# untitled.net
KiCad netlist of a schematic drawn in EAGLE
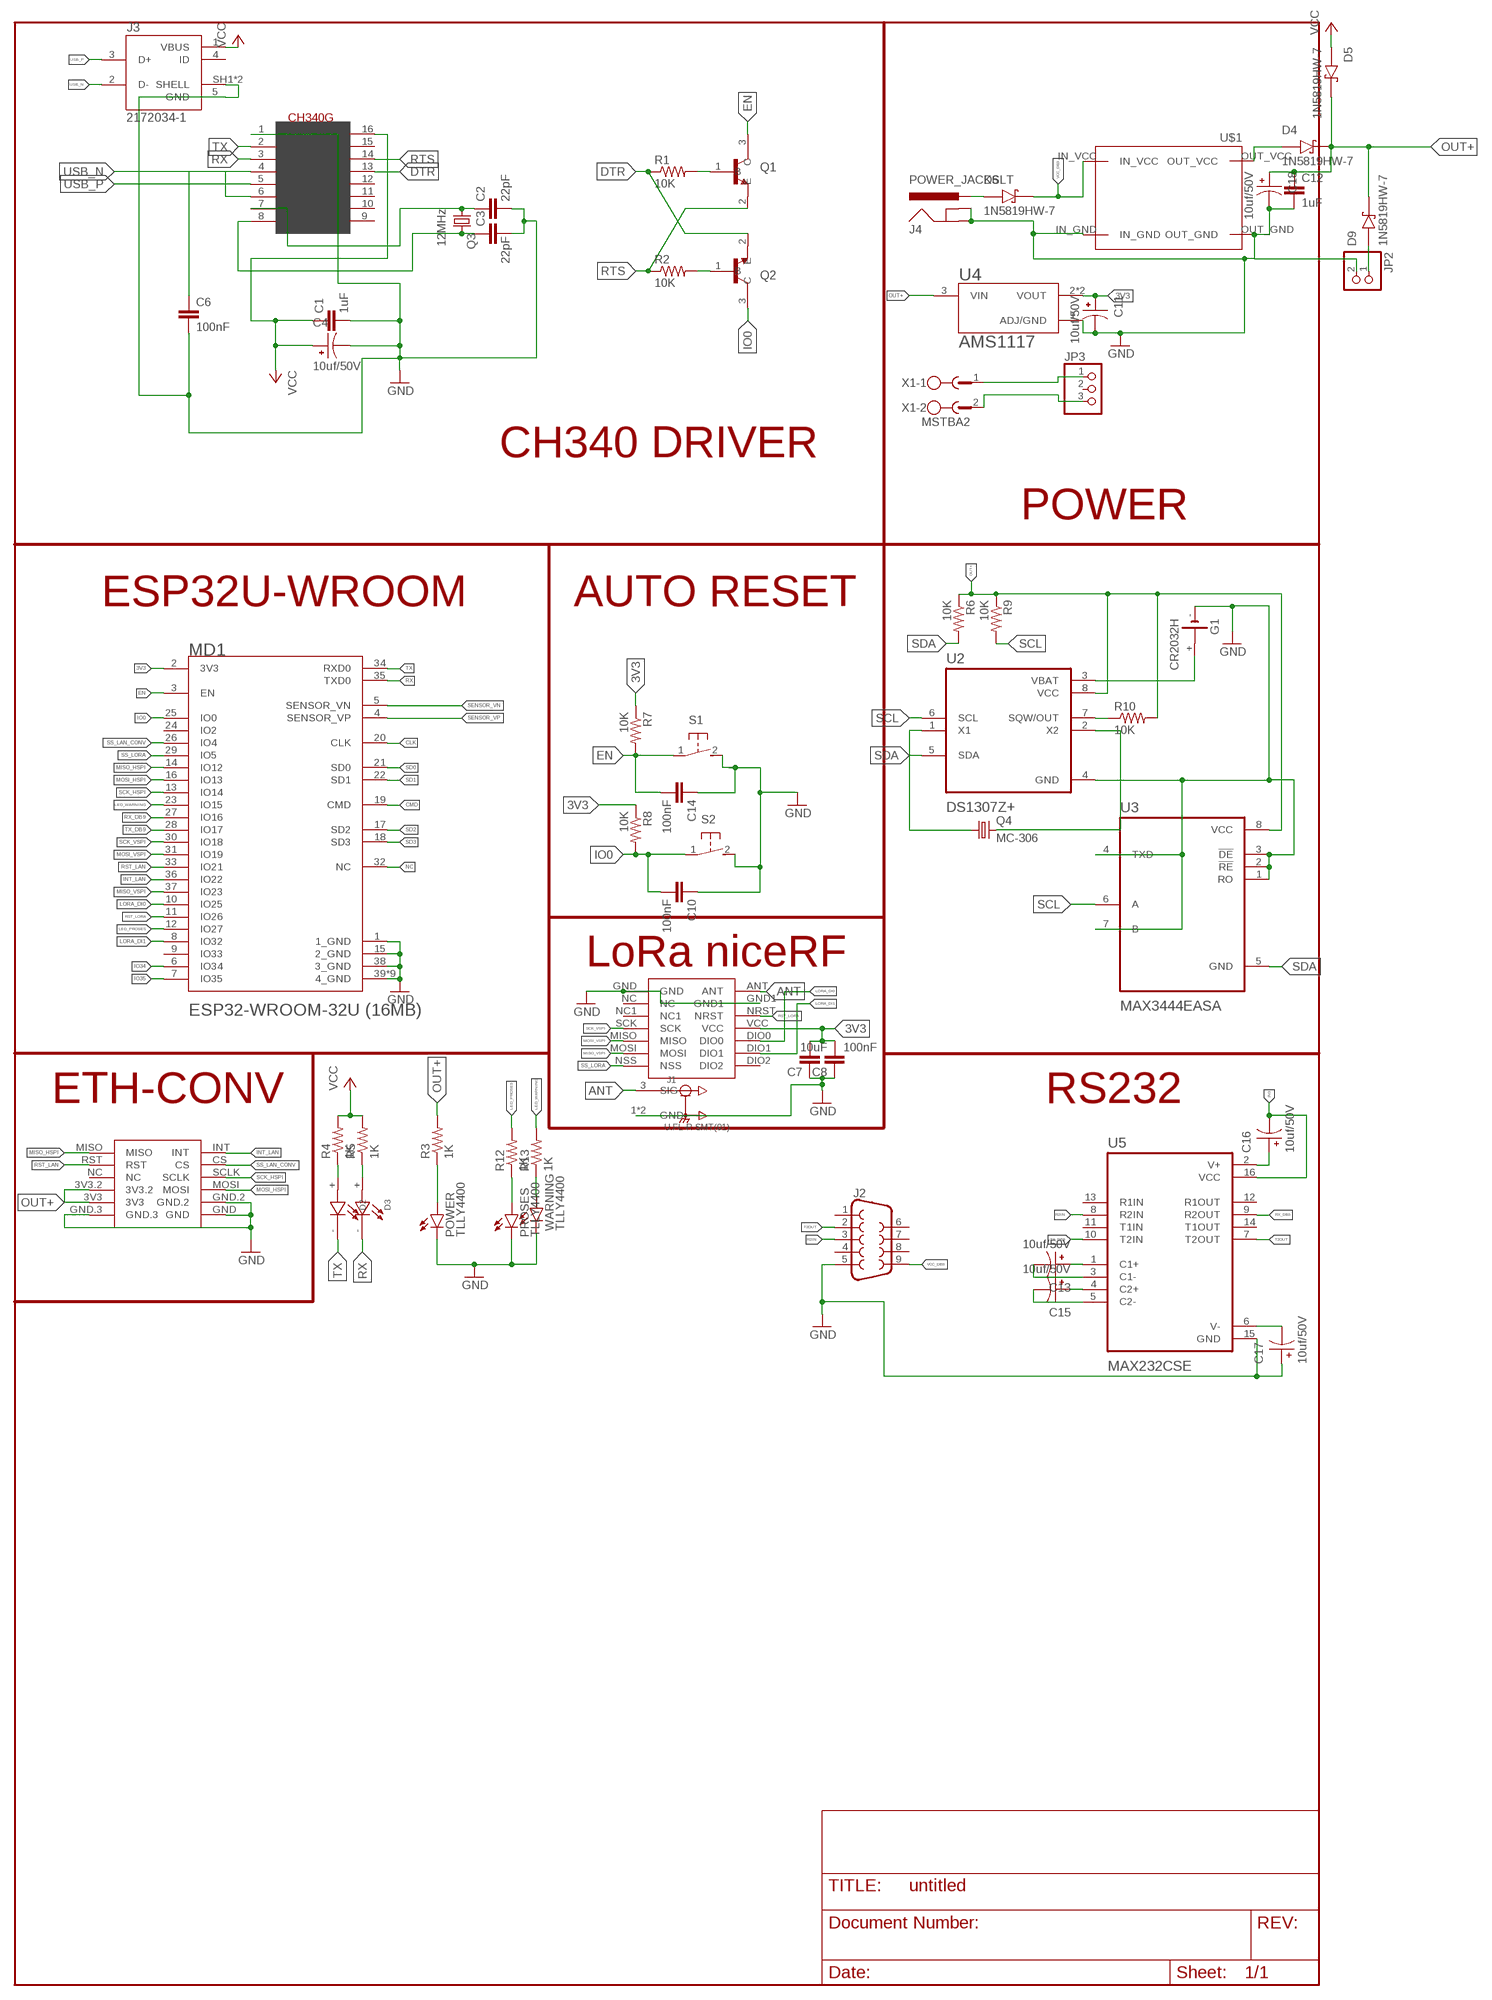
[diagram p0: schematic, sheet 1]

(export (version "E")
  (design (tool "Eeschema 10.0.6"))
  (components
    (comp (ref "C1")
      (value "1uF")
      (footprint "eagle-import:C0805K")
      (libsource (lib "eagle-import") (part "C-EUC0805K"))
    )
    (comp (ref "C2")
      (value "22pF")
      (footprint "eagle-import:C0805K")
      (libsource (lib "eagle-import") (part "C-EUC0805K"))
    )
    (comp (ref "C3")
      (value "22pF")
      (footprint "eagle-import:C0805K")
      (libsource (lib "eagle-import") (part "C-EUC0805K"))
    )
    (comp (ref "C4")
      (value "10uf/50V")
      (footprint "eagle-import:CAP_EEEFK1H100V")
      (fields (field (name "MF") "Panasonic") (field (name "MP") "EEEFK1H100V"))
      (libsource (lib "eagle-import") (part "EEEFK1H100V"))
    )
    (comp (ref "C6")
      (value "100nF")
      (footprint "eagle-import:C0805K")
      (libsource (lib "eagle-import") (part "C-EUC0805K"))
    )
    (comp (ref "C7")
      (value "10uF")
      (footprint "eagle-import:C0805K")
      (libsource (lib "eagle-import") (part "C-EUC0805K"))
    )
    (comp (ref "C8")
      (value "100nF")
      (footprint "eagle-import:C0805K")
      (libsource (lib "eagle-import") (part "C-EUC0805K"))
    )
    (comp (ref "C10")
      (value "100nF")
      (footprint "eagle-import:C0805K")
      (libsource (lib "eagle-import") (part "C-EUC0805K"))
    )
    (comp (ref "C11")
      (value "10uf/50V")
      (footprint "eagle-import:CAP_EEEFK1H100V")
      (fields (field (name "MF") "Panasonic") (field (name "MP") "EEEFK1H100V"))
      (libsource (lib "eagle-import") (part "EEEFK1H100V"))
    )
    (comp (ref "C12")
      (value "1uF")
      (footprint "eagle-import:C0805K")
      (libsource (lib "eagle-import") (part "C-EUC0805K"))
    )
    (comp (ref "C13")
      (value "10uf/50V")
      (footprint "eagle-import:CAP_EEEFK1H100V")
      (fields (field (name "MF") "Panasonic") (field (name "MP") "EEEFK1H100V"))
      (libsource (lib "eagle-import") (part "EEEFK1H100V"))
    )
    (comp (ref "C14")
      (value "100nF")
      (footprint "eagle-import:C0805K")
      (libsource (lib "eagle-import") (part "C-EUC0805K"))
    )
    (comp (ref "C15")
      (value "10uf/50V")
      (footprint "eagle-import:CAP_EEEFK1H100V")
      (fields (field (name "MF") "Panasonic") (field (name "MP") "EEEFK1H100V"))
      (libsource (lib "eagle-import") (part "EEEFK1H100V"))
    )
    (comp (ref "C16")
      (value "10uf/50V")
      (footprint "eagle-import:CAP_EEEFK1H100V")
      (fields (field (name "MF") "Panasonic") (field (name "MP") "EEEFK1H100V"))
      (libsource (lib "eagle-import") (part "EEEFK1H100V"))
    )
    (comp (ref "C17")
      (value "10uf/50V")
      (footprint "eagle-import:CAP_EEEFK1H100V")
      (fields (field (name "MF") "Panasonic") (field (name "MP") "EEEFK1H100V"))
      (libsource (lib "eagle-import") (part "EEEFK1H100V"))
    )
    (comp (ref "C18")
      (value "10uf/50V")
      (footprint "eagle-import:CAP_EEEFK1H100V")
      (fields (field (name "MF") "Panasonic") (field (name "MP") "EEEFK1H100V"))
      (libsource (lib "eagle-import") (part "EEEFK1H100V"))
    )
    (comp (ref "D2")
      (value "Tx")
      (footprint "eagle-import:LEDC3216X120N")
      (fields (field (name "MF") "Osram") (field (name "MP") "LHN974 RED LED 1206"))
      (libsource (lib "eagle-import") (part "LHN974_RED_LED_1206"))
    )
    (comp (ref "D3")
      (value "Rx")
      (footprint "eagle-import:LEDC3216X120N")
      (fields (field (name "MF") "Osram") (field (name "MP") "LHN974 RED LED 1206"))
      (libsource (lib "eagle-import") (part "LHN974_RED_LED_1206"))
    )
    (comp (ref "D4")
      (value "1N5819HW-7")
      (footprint "eagle-import:SOD3715X145N")
      (fields (field (name "MF") "Diodes Inc."))
      (libsource (lib "eagle-import") (part "1N5819HW-7"))
    )
    (comp (ref "D5")
      (value "1N5819HW-7")
      (footprint "eagle-import:SOD3715X145N")
      (fields (field (name "MF") "Diodes Inc."))
      (libsource (lib "eagle-import") (part "1N5819HW-7"))
    )
    (comp (ref "D6")
      (value "1N5819HW-7")
      (footprint "eagle-import:SOD3715X145N")
      (fields (field (name "MF") "Diodes Inc."))
      (libsource (lib "eagle-import") (part "1N5819HW-7"))
    )
    (comp (ref "D9")
      (value "1N5819HW-7")
      (footprint "eagle-import:SOD3715X145N")
      (fields (field (name "MF") "Diodes Inc."))
      (libsource (lib "eagle-import") (part "1N5819HW-7"))
    )
    (comp (ref "G1")
      (value "CR2032H")
      (footprint "eagle-import:CR2032H")
      (libsource (lib "eagle-import") (part "CR2032H"))
    )
    (comp (ref "J1")
      (value "U.FL-R-SMT(01)")
      (footprint "eagle-import:HRS_U.FL-R-SMT(01)")
      (fields (field (name "MF") "Hirose"))
      (libsource (lib "eagle-import") (part "U.FL-R-SMT(01)"))
    )
    (comp (ref "J2")
      (value "DB9FEMALE")
      (footprint "eagle-import:DB9")
      (libsource (lib "eagle-import") (part "DB9FEMALE"))
    )
    (comp (ref "J3")
      (value "2172034-1")
      (footprint "eagle-import:TE_2172034-1")
      (fields (field (name "MF") "TE Connectivity"))
      (libsource (lib "eagle-import") (part "2172034-1"))
    )
    (comp (ref "J4")
      (value "POWER_JACKSLT")
      (footprint "eagle-import:POWER_JACK_SLOT")
      (libsource (lib "eagle-import") (part "POWER_JACKSLT"))
    )
    (comp (ref "JP2")
      (value "PINHD-1X2")
      (footprint "eagle-import:1X02")
      (libsource (lib "eagle-import") (part "PINHD-1X2"))
    )
    (comp (ref "JP3")
      (value "PINHD-1X3")
      (footprint "eagle-import:1X03")
      (libsource (lib "eagle-import") (part "PINHD-1X3"))
    )
    (comp (ref "LORA-NICERF-V1")
      (value "LORA-NICERF-V2")
      (footprint "eagle-import:LORA-NICERF-V2")
      (libsource (lib "eagle-import") (part "LORA-NICERF-V2"))
    )
    (comp (ref "MD1")
      (value "ESPRESSIF_SYSTEMS_ESP32-WROOM-32U_16MBESPRESSIF_SYSTEMS_ESP32-WROOM-32U_16MB_0_0")
      (footprint "eagle-import:ESPRESSIF_SYSTEMS_ESP32-WROOM-32U_16MB_0")
      (fields
        (field (name "DIGIKEY_PART_NUMBER") "1904-1028-1-ND")
        (field (name "MF") "Espressif Systems")
        (field (name "MOUSER_PART_NUMBER") "356-ES32WROOM32U16MB")
      )
      (libsource (lib "eagle-import") (part "ESPRESSIF_SYSTEMS_ESP32-WROOM-32U_16MBESPRESSIF_SYSTEMS_ESP32-WROOM-32U_16MB_0_0"))
    )
    (comp (ref "POWER")
      (value "TLLY4400")
      (footprint "eagle-import:LED3MM")
      (fields (field (name "MF") "VISHAY SEMICONDUCTOR"))
      (libsource (lib "eagle-import") (part "TLLY4400"))
    )
    (comp (ref "PROSES")
      (value "TLLY4400")
      (footprint "eagle-import:LED3MM")
      (fields (field (name "MF") "VISHAY SEMICONDUCTOR"))
      (libsource (lib "eagle-import") (part "TLLY4400"))
    )
    (comp (ref "Q1")
      (value "MMBT3904")
      (footprint "eagle-import:SOT95P240X120-3N")
      (fields (field (name "MF") "STMicroelectronics"))
      (libsource (lib "eagle-import") (part "MMBT3904"))
    )
    (comp (ref "Q2")
      (value "MMBT3904")
      (footprint "eagle-import:SOT95P240X120-3N")
      (fields (field (name "MF") "STMicroelectronics"))
      (libsource (lib "eagle-import") (part "MMBT3904"))
    )
    (comp (ref "Q3")
      (value "12MHz")
      (footprint "eagle-import:SM49")
      (libsource (lib "eagle-import") (part "CRYSTALSM49"))
    )
    (comp (ref "Q4")
      (value "MC-306")
      (footprint "eagle-import:MC-306")
      (fields (field (name "MPN") "MC-306 60.0KHZ  100PPM ,12.5PF"))
      (libsource (lib "eagle-import") (part "MC-306"))
    )
    (comp (ref "R1")
      (value "10K")
      (footprint "eagle-import:M0805")
      (libsource (lib "eagle-import") (part "R-US_M0805"))
    )
    (comp (ref "R2")
      (value "10K")
      (footprint "eagle-import:M0805")
      (libsource (lib "eagle-import") (part "R-US_M0805"))
    )
    (comp (ref "R3")
      (value "1K")
      (footprint "eagle-import:M0805")
      (libsource (lib "eagle-import") (part "R-US_M0805"))
    )
    (comp (ref "R4")
      (value "1K")
      (footprint "eagle-import:M0805")
      (libsource (lib "eagle-import") (part "R-US_M0805"))
    )
    (comp (ref "R5")
      (value "1K")
      (footprint "eagle-import:M0805")
      (libsource (lib "eagle-import") (part "R-US_M0805"))
    )
    (comp (ref "R6")
      (value "10K")
      (footprint "eagle-import:M0805")
      (libsource (lib "eagle-import") (part "R-US_M0805"))
    )
    (comp (ref "R7")
      (value "10K")
      (footprint "eagle-import:M0805")
      (libsource (lib "eagle-import") (part "R-US_M0805"))
    )
    (comp (ref "R8")
      (value "10K")
      (footprint "eagle-import:M0805")
      (libsource (lib "eagle-import") (part "R-US_M0805"))
    )
    (comp (ref "R9")
      (value "10K")
      (footprint "eagle-import:M0805")
      (libsource (lib "eagle-import") (part "R-US_M0805"))
    )
    (comp (ref "R10")
      (value "10K")
      (footprint "eagle-import:M0805")
      (libsource (lib "eagle-import") (part "R-US_M0805"))
    )
    (comp (ref "R12")
      (value "1K")
      (footprint "eagle-import:M0805")
      (libsource (lib "eagle-import") (part "R-US_M0805"))
    )
    (comp (ref "R13")
      (value "1K")
      (footprint "eagle-import:M0805")
      (libsource (lib "eagle-import") (part "R-US_M0805"))
    )
    (comp (ref "S1")
      (value "31-XX")
      (footprint "eagle-import:B3F-31XX")
      (fields (field (name "MPN") "B3F-3100"))
      (libsource (lib "eagle-import") (part "31-XX"))
    )
    (comp (ref "S2")
      (value "31-XX")
      (footprint "eagle-import:B3F-31XX")
      (fields (field (name "MPN") "B3F-3100"))
      (libsource (lib "eagle-import") (part "31-XX"))
    )
    (comp (ref "U$1")
      (value "STEPDOWN_SY8205")
      (footprint "eagle-import:STEPDOWN_SY8205")
      (libsource (lib "eagle-import") (part "STEPDOWN_SY8205"))
    )
    (comp (ref "U$2")
      (value "CH340G")
      (footprint "eagle-import:SOIC16")
      (libsource (lib "eagle-import") (part "CH340G"))
    )
    (comp (ref "U$3")
      (value "MINI_W5500")
      (footprint "eagle-import:MINI_W5500")
      (libsource (lib "eagle-import") (part "MINI_W5500"))
    )
    (comp (ref "U2")
      (value "DS1307Z+")
      (footprint "eagle-import:SOIC127P600X175-8N")
      (fields (field (name "MF") "Maxim Integrated") (field (name "MP") "DS1307Z"))
      (libsource (lib "eagle-import") (part "DS1307Z+"))
    )
    (comp (ref "U3")
      (value "MAX3444EASA")
      (footprint "eagle-import:SOIC127P600X175-8N")
      (fields (field (name "MF") "Maxim Integrated") (field (name "MP") "MAX3444EASA+"))
      (libsource (lib "eagle-import") (part "MAX3444EASA"))
    )
    (comp (ref "U4")
      (value "AMS1117")
      (footprint "eagle-import:SOT229P700X180-4N")
      (fields (field (name "MF") "Advanced Monolithic Systems"))
      (libsource (lib "eagle-import") (part "AMS1117"))
    )
    (comp (ref "U5")
      (value "MAX232CSE")
      (footprint "eagle-import:SOIC127P600X175-16N")
      (fields (field (name "MF") "Maxim Integrated"))
      (libsource (lib "eagle-import") (part "MAX232CSE"))
    )
    (comp (ref "WARNING")
      (value "TLLY4400")
      (footprint "eagle-import:LED3MM")
      (fields (field (name "MF") "VISHAY SEMICONDUCTOR"))
      (libsource (lib "eagle-import") (part "TLLY4400"))
    )
    (comp (ref "X1")
      (value "MSTBA2")
      (footprint "eagle-import:MSTBA2")
      (fields (field (name "MF") "FARNELL") (field (name "MPN") "1757242"))
      (libsource (lib "eagle-import") (part "MSTBA2"))
    )
  )
  (nets
    (net (code "1") (name "3V3") (class "Default")
      (node (ref "C11") (pin "1") (pinfunction "1_1") (pintype "passive"))
      (node (ref "C16") (pin "2") (pinfunction "2_2") (pintype "passive"))
      (node (ref "C7") (pin "2") (pinfunction "2_2") (pintype "passive"))
      (node (ref "C8") (pin "2") (pinfunction "2_2") (pintype "passive"))
      (node (ref "LORA-NICERF-V1") (pin "VCC") (pinfunction "VCC_VCC") (pintype "bidirectional"))
      (node (ref "MD1") (pin "2") (pinfunction "3V3_2") (pintype "power_in"))
      (node (ref "R7") (pin "1") (pinfunction "1_1") (pintype "passive"))
      (node (ref "R8") (pin "1") (pinfunction "1_1") (pintype "passive"))
      (node (ref "U4") (pin "2") (pinfunction "VOUT_2") (pintype "output"))
      (node (ref "U4") (pin "4") (pinfunction "VOUT_4") (pintype "output"))
      (node (ref "U5") (pin "16") (pinfunction "VCC_16") (pintype "power_in"))
    )
    (net (code "2") (name "ANT") (class "Default")
      (node (ref "J1") (pin "3") (pinfunction "SIG_3") (pintype "passive"))
      (node (ref "LORA-NICERF-V1") (pin "ANT") (pinfunction "ANT_ANT") (pintype "bidirectional"))
    )
    (net (code "3") (name "CLK") (class "Default")
      (node (ref "MD1") (pin "20") (pinfunction "CLK_20") (pintype "bidirectional"))
    )
    (net (code "4") (name "CMD") (class "Default")
      (node (ref "MD1") (pin "19") (pinfunction "CMD_19") (pintype "bidirectional"))
    )
    (net (code "5") (name "DTR") (class "Default")
      (node (ref "Q2") (pin "2") (pinfunction "E_2") (pintype "passive"))
      (node (ref "R1") (pin "1") (pinfunction "1_1") (pintype "passive"))
      (node (ref "U$2") (pin "13") (pinfunction "DTR_13") (pintype "bidirectional"))
    )
    (net (code "6") (name "EN") (class "Default")
      (node (ref "C14") (pin "2") (pinfunction "2_2") (pintype "passive"))
      (node (ref "MD1") (pin "3") (pinfunction "EN_3") (pintype "input"))
      (node (ref "Q1") (pin "3") (pinfunction "C_3") (pintype "passive"))
      (node (ref "R7") (pin "2") (pinfunction "2_2") (pintype "passive"))
      (node (ref "S1") (pin "1") (pinfunction "P_1") (pintype "passive"))
    )
    (net (code "7") (name "GND") (class "Default")
      (node (ref "C1") (pin "2") (pinfunction "2_2") (pintype "passive"))
      (node (ref "C10") (pin "1") (pinfunction "1_1") (pintype "passive"))
      (node (ref "C11") (pin "2") (pinfunction "2_2") (pintype "passive"))
      (node (ref "C12") (pin "2") (pinfunction "2_2") (pintype "passive"))
      (node (ref "C14") (pin "1") (pinfunction "1_1") (pintype "passive"))
      (node (ref "C17") (pin "1") (pinfunction "1_1") (pintype "passive"))
      (node (ref "C18") (pin "2") (pinfunction "2_2") (pintype "passive"))
      (node (ref "C2") (pin "2") (pinfunction "2_2") (pintype "passive"))
      (node (ref "C3") (pin "2") (pinfunction "2_2") (pintype "passive"))
      (node (ref "C4") (pin "2") (pinfunction "2_2") (pintype "passive"))
      (node (ref "C6") (pin "2") (pinfunction "2_2") (pintype "passive"))
      (node (ref "C7") (pin "1") (pinfunction "1_1") (pintype "passive"))
      (node (ref "C8") (pin "1") (pinfunction "1_1") (pintype "passive"))
      (node (ref "G1") (pin "-") (pinfunction "-_-") (pintype "passive"))
      (node (ref "J1") (pin "1") (pinfunction "GND_1") (pintype "passive"))
      (node (ref "J1") (pin "2") (pinfunction "GND_2") (pintype "passive"))
      (node (ref "J2") (pin "5") (pinfunction "5_5") (pintype "passive"))
      (node (ref "J3") (pin "5") (pinfunction "GND_5") (pintype "power_in"))
      (node (ref "J3") (pin "SH1") (pinfunction "SHELL_SH1") (pintype "power_in"))
      (node (ref "J3") (pin "SH2") (pinfunction "SHELL_SH2") (pintype "power_in"))
      (node (ref "J4") (pin "GND@1") (pinfunction "GNDBREAK_GND@1") (pintype "bidirectional"))
      (node (ref "J4") (pin "GND@2") (pinfunction "GND_GND@2") (pintype "bidirectional"))
      (node (ref "JP2") (pin "2") (pinfunction "2_2") (pintype "passive"))
      (node (ref "LORA-NICERF-V1") (pin "GND") (pinfunction "GND_GND") (pintype "bidirectional"))
      (node (ref "LORA-NICERF-V1") (pin "GND1") (pinfunction "GND1_GND1") (pintype "bidirectional"))
      (node (ref "MD1") (pin "1") (pinfunction "1_GND_1") (pintype "power_in"))
      (node (ref "MD1") (pin "15") (pinfunction "2_GND_15") (pintype "power_in"))
      (node (ref "MD1") (pin "38") (pinfunction "3_GND_38") (pintype "power_in"))
      (node (ref "MD1") (pin "39") (pinfunction "4_GND_39") (pintype "power_in"))
      (node (ref "MD1") (pin "39-2") (pinfunction "4_GND_39-2") (pintype "power_in"))
      (node (ref "MD1") (pin "39-3") (pinfunction "4_GND_39-3") (pintype "power_in"))
      (node (ref "MD1") (pin "39-4") (pinfunction "4_GND_39-4") (pintype "power_in"))
      (node (ref "MD1") (pin "39-5") (pinfunction "4_GND_39-5") (pintype "power_in"))
      (node (ref "MD1") (pin "39-6") (pinfunction "4_GND_39-6") (pintype "power_in"))
      (node (ref "MD1") (pin "39-7") (pinfunction "4_GND_39-7") (pintype "power_in"))
      (node (ref "MD1") (pin "39-8") (pinfunction "4_GND_39-8") (pintype "power_in"))
      (node (ref "MD1") (pin "39-9") (pinfunction "4_GND_39-9") (pintype "power_in"))
      (node (ref "POWER") (pin "K") (pinfunction "C_K") (pintype "passive"))
      (node (ref "PROSES") (pin "K") (pinfunction "C_K") (pintype "passive"))
      (node (ref "S1") (pin "2") (pinfunction "S_2") (pintype "passive"))
      (node (ref "S2") (pin "2") (pinfunction "S_2") (pintype "passive"))
      (node (ref "U$1") (pin "IN_GND") (pinfunction "IN_GND_IN_GND") (pintype "bidirectional"))
      (node (ref "U$1") (pin "OUT_GND") (pinfunction "OUT_GND_OUT_GND") (pintype "bidirectional"))
      (node (ref "U$2") (pin "1") (pinfunction "GND_1") (pintype "bidirectional"))
      (node (ref "U$3") (pin "GND") (pinfunction "GND_GND") (pintype "bidirectional"))
      (node (ref "U$3") (pin "GND.2") (pinfunction "GND.2_GND.2") (pintype "bidirectional"))
      (node (ref "U$3") (pin "GND.3") (pinfunction "GND.3_GND.3") (pintype "bidirectional"))
      (node (ref "U2") (pin "4") (pinfunction "GND_4") (pintype "power_in"))
      (node (ref "U3") (pin "1") (pinfunction "RO_1") (pintype "output"))
      (node (ref "U3") (pin "2") (pinfunction "~{RE}_2") (pintype "output"))
      (node (ref "U3") (pin "3") (pinfunction "~{DE}_3") (pintype "output"))
      (node (ref "U3") (pin "4") (pinfunction "TXD_4") (pintype "input"))
      (node (ref "U3") (pin "7") (pinfunction "B_7") (pintype "bidirectional"))
      (node (ref "U4") (pin "1") (pinfunction "ADJ/GND_1") (pintype "power_in"))
      (node (ref "U5") (pin "15") (pinfunction "GND_15") (pintype "power_in"))
      (node (ref "WARNING") (pin "K") (pinfunction "C_K") (pintype "passive"))
    )
    (net (code "8") (name "INT_LAN") (class "Default")
      (node (ref "MD1") (pin "36") (pinfunction "IO22_36") (pintype "bidirectional"))
      (node (ref "U$3") (pin "INT") (pinfunction "INT_INT") (pintype "bidirectional"))
    )
    (net (code "9") (name "IO0") (class "Default")
      (node (ref "C10") (pin "2") (pinfunction "2_2") (pintype "passive"))
      (node (ref "MD1") (pin "25") (pinfunction "IO0_25") (pintype "bidirectional"))
      (node (ref "Q2") (pin "3") (pinfunction "C_3") (pintype "passive"))
      (node (ref "R8") (pin "2") (pinfunction "2_2") (pintype "passive"))
      (node (ref "S2") (pin "1") (pinfunction "P_1") (pintype "passive"))
    )
    (net (code "10") (name "IO34") (class "Default")
      (node (ref "MD1") (pin "6") (pinfunction "IO34_6") (pintype "bidirectional"))
    )
    (net (code "11") (name "IO35") (class "Default")
      (node (ref "MD1") (pin "7") (pinfunction "IO35_7") (pintype "bidirectional"))
    )
    (net (code "12") (name "LED_PROSES") (class "Default")
      (node (ref "MD1") (pin "12") (pinfunction "IO27_12") (pintype "bidirectional"))
      (node (ref "R12") (pin "2") (pinfunction "2_2") (pintype "passive"))
    )
    (net (code "13") (name "LED_WARNING") (class "Default")
      (node (ref "MD1") (pin "23") (pinfunction "IO15_23") (pintype "bidirectional"))
      (node (ref "R13") (pin "2") (pinfunction "2_2") (pintype "passive"))
    )
    (net (code "14") (name "LORA_DI0") (class "Default")
      (node (ref "LORA-NICERF-V1") (pin "DIO0") (pinfunction "DIO0_DIO0") (pintype "bidirectional"))
      (node (ref "MD1") (pin "10") (pinfunction "IO25_10") (pintype "bidirectional"))
    )
    (net (code "15") (name "LORA_DI1") (class "Default")
      (node (ref "LORA-NICERF-V1") (pin "DIO1") (pinfunction "DIO1_DIO1") (pintype "bidirectional"))
      (node (ref "MD1") (pin "8") (pinfunction "IO32_8") (pintype "bidirectional"))
    )
    (net (code "16") (name "MISO_HSPI") (class "Default")
      (node (ref "MD1") (pin "14") (pinfunction "IO12_14") (pintype "bidirectional"))
      (node (ref "U$3") (pin "MISO") (pinfunction "MISO_MISO") (pintype "bidirectional"))
    )
    (net (code "17") (name "MISO_VSPI") (class "Default")
      (node (ref "LORA-NICERF-V1") (pin "MOSI") (pinfunction "MOSI_MOSI") (pintype "bidirectional"))
      (node (ref "MD1") (pin "37") (pinfunction "IO23_37") (pintype "bidirectional"))
    )
    (net (code "18") (name "MOSI_HSPI") (class "Default")
      (node (ref "MD1") (pin "16") (pinfunction "IO13_16") (pintype "bidirectional"))
      (node (ref "U$3") (pin "MOSI") (pinfunction "MOSI_MOSI") (pintype "bidirectional"))
    )
    (net (code "19") (name "MOSI_VSPI") (class "Default")
      (node (ref "LORA-NICERF-V1") (pin "MISO") (pinfunction "MISO_MISO") (pintype "bidirectional"))
      (node (ref "MD1") (pin "31") (pinfunction "IO19_31") (pintype "bidirectional"))
    )
    (net (code "20") (name "NC") (class "Default")
      (node (ref "MD1") (pin "32") (pinfunction "NC_32") (pintype "passive"))
    )
    (net (code "21") (name "Net-(D2-Pad+)") (class "Default")
      (node (ref "D2") (pin "+") (pinfunction "+_+") (pintype "passive"))
      (node (ref "R4") (pin "1") (pinfunction "1_1") (pintype "passive"))
    )
    (net (code "22") (name "Net-(D3-Pad+)") (class "Default")
      (node (ref "D3") (pin "+") (pinfunction "+_+") (pintype "passive"))
      (node (ref "R5") (pin "1") (pinfunction "1_1") (pintype "passive"))
    )
    (net (code "23") (name "Net-(D4-PadA)") (class "Default")
      (node (ref "D4") (pin "A") (pinfunction "A_A") (pintype "passive"))
      (node (ref "U$1") (pin "OUT_VCC") (pinfunction "OUT_VCC_OUT_VCC") (pintype "bidirectional"))
    )
    (net (code "24") (name "Net-(D6-PadA)") (class "Default")
      (node (ref "D6") (pin "A") (pinfunction "A_A") (pintype "passive"))
      (node (ref "J4") (pin "PWR") (pinfunction "PWR_PWR") (pintype "bidirectional"))
    )
    (net (code "25") (name "Net-(D9-PadA)") (class "Default")
      (node (ref "D9") (pin "A") (pinfunction "A_A") (pintype "passive"))
      (node (ref "JP2") (pin "1") (pinfunction "1_1") (pintype "passive"))
    )
    (net (code "26") (name "Net-(JP3-Pad1)") (class "Default")
      (node (ref "JP3") (pin "1") (pinfunction "1_1") (pintype "passive"))
      (node (ref "X1") (pin "1") (pinfunction "1_1") (pintype "passive"))
    )
    (net (code "27") (name "Net-(POWER-PadA)") (class "Default")
      (node (ref "POWER") (pin "A") (pinfunction "A_A") (pintype "passive"))
      (node (ref "R3") (pin "1") (pinfunction "1_1") (pintype "passive"))
    )
    (net (code "28") (name "Net-(PROSES-PadA)") (class "Default")
      (node (ref "PROSES") (pin "A") (pinfunction "A_A") (pintype "passive"))
      (node (ref "R12") (pin "1") (pinfunction "1_1") (pintype "passive"))
    )
    (net (code "29") (name "Net-(Q1-B)") (class "Default")
      (node (ref "Q1") (pin "1") (pinfunction "B_1") (pintype "passive"))
      (node (ref "R1") (pin "2") (pinfunction "2_2") (pintype "passive"))
    )
    (net (code "30") (name "Net-(Q2-B)") (class "Default")
      (node (ref "Q2") (pin "1") (pinfunction "B_1") (pintype "passive"))
      (node (ref "R2") (pin "2") (pinfunction "2_2") (pintype "passive"))
    )
    (net (code "31") (name "Net-(Q4-2)") (class "Default")
      (node (ref "Q4") (pin "4") (pinfunction "2_4") (pintype "passive"))
      (node (ref "U2") (pin "2") (pinfunction "X2_2") (pintype "output"))
    )
    (net (code "32") (name "Net-(R13-Pad1)") (class "Default")
      (node (ref "R13") (pin "1") (pinfunction "1_1") (pintype "passive"))
      (node (ref "WARNING") (pin "A") (pinfunction "A_A") (pintype "passive"))
    )
    (net (code "33") (name "Net-(U$2-V3)") (class "Default")
      (node (ref "C6") (pin "1") (pinfunction "1_1") (pintype "passive"))
      (node (ref "U$2") (pin "4") (pinfunction "V3_4") (pintype "bidirectional"))
    )
    (net (code "34") (name "Net-(U$2-XI)") (class "Default")
      (node (ref "C2") (pin "1") (pinfunction "1_1") (pintype "passive"))
      (node (ref "Q3") (pin "1") (pinfunction "1_1") (pintype "passive"))
      (node (ref "U$2") (pin "7") (pinfunction "XI_7") (pintype "bidirectional"))
    )
    (net (code "35") (name "Net-(U$2-XO)") (class "Default")
      (node (ref "C3") (pin "1") (pinfunction "1_1") (pintype "passive"))
      (node (ref "Q3") (pin "2") (pinfunction "2_2") (pintype "passive"))
      (node (ref "U$2") (pin "8") (pinfunction "XO_8") (pintype "bidirectional"))
    )
    (net (code "36") (name "Net-(U2-SQW{slash}OUT)") (class "Default")
      (node (ref "R10") (pin "1") (pinfunction "1_1") (pintype "passive"))
      (node (ref "U2") (pin "7") (pinfunction "SQW/OUT_7") (pintype "output"))
    )
    (net (code "37") (name "Net-(U2-VBAT)") (class "Default")
      (node (ref "G1") (pin "+") (pinfunction "+_+") (pintype "passive"))
      (node (ref "U2") (pin "3") (pinfunction "VBAT_3") (pintype "power_in"))
    )
    (net (code "38") (name "Net-(U2-X1)") (class "Default")
      (node (ref "Q4") (pin "1") (pinfunction "1_1") (pintype "passive"))
      (node (ref "U2") (pin "1") (pinfunction "X1_1") (pintype "input"))
    )
    (net (code "39") (name "Net-(U5-C1+)") (class "Default")
      (node (ref "C13") (pin "1") (pinfunction "1_1") (pintype "passive"))
      (node (ref "U5") (pin "1") (pinfunction "C1+_1") (pintype "bidirectional"))
    )
    (net (code "40") (name "Net-(U5-C1-)") (class "Default")
      (node (ref "C13") (pin "2") (pinfunction "2_2") (pintype "passive"))
      (node (ref "U5") (pin "3") (pinfunction "C1-_3") (pintype "bidirectional"))
    )
    (net (code "41") (name "Net-(U5-C2+)") (class "Default")
      (node (ref "C15") (pin "1") (pinfunction "1_1") (pintype "passive"))
      (node (ref "U5") (pin "4") (pinfunction "C2+_4") (pintype "bidirectional"))
    )
    (net (code "42") (name "Net-(U5-C2-)") (class "Default")
      (node (ref "C15") (pin "2") (pinfunction "2_2") (pintype "passive"))
      (node (ref "U5") (pin "5") (pinfunction "C2-_5") (pintype "bidirectional"))
    )
    (net (code "43") (name "Net-(U5-V+)") (class "Default")
      (node (ref "C16") (pin "1") (pinfunction "1_1") (pintype "passive"))
      (node (ref "U5") (pin "2") (pinfunction "V+_2") (pintype "power_in"))
    )
    (net (code "44") (name "Net-(U5-V-)") (class "Default")
      (node (ref "C17") (pin "2") (pinfunction "2_2") (pintype "passive"))
      (node (ref "U5") (pin "6") (pinfunction "V-_6") (pintype "power_in"))
    )
    (net (code "45") (name "Net-(X1B-1)") (class "Default")
      (node (ref "JP3") (pin "3") (pinfunction "3_3") (pintype "passive"))
      (node (ref "X1") (pin "2") (pinfunction "1_2") (pintype "passive"))
    )
    (net (code "46") (name "OUT+") (class "Default")
      (node (ref "C12") (pin "1") (pinfunction "1_1") (pintype "passive"))
      (node (ref "C18") (pin "1") (pinfunction "1_1") (pintype "passive"))
      (node (ref "D4") (pin "C") (pinfunction "K_C") (pintype "passive"))
      (node (ref "D5") (pin "C") (pinfunction "K_C") (pintype "passive"))
      (node (ref "D9") (pin "C") (pinfunction "K_C") (pintype "passive"))
      (node (ref "R10") (pin "2") (pinfunction "2_2") (pintype "passive"))
      (node (ref "R3") (pin "2") (pinfunction "2_2") (pintype "passive"))
      (node (ref "R6") (pin "1") (pinfunction "1_1") (pintype "passive"))
      (node (ref "R9") (pin "1") (pinfunction "1_1") (pintype "passive"))
      (node (ref "U$3") (pin "3V3") (pinfunction "3V3_3V3") (pintype "bidirectional"))
      (node (ref "U$3") (pin "3V3.2") (pinfunction "3V3.2_3V3.2") (pintype "bidirectional"))
      (node (ref "U2") (pin "8") (pinfunction "VCC_8") (pintype "power_in"))
      (node (ref "U3") (pin "8") (pinfunction "VCC_8") (pintype "power_in"))
      (node (ref "U4") (pin "3") (pinfunction "VIN_3") (pintype "input"))
    )
    (net (code "47") (name "R2IN") (class "Default")
      (node (ref "J2") (pin "3") (pinfunction "3_3") (pintype "passive"))
      (node (ref "U5") (pin "8") (pinfunction "R2IN_8") (pintype "input"))
    )
    (net (code "48") (name "RST_LAN") (class "Default")
      (node (ref "MD1") (pin "33") (pinfunction "IO21_33") (pintype "bidirectional"))
      (node (ref "U$3") (pin "RST") (pinfunction "RST_RST") (pintype "bidirectional"))
    )
    (net (code "49") (name "RST_LORA") (class "Default")
      (node (ref "LORA-NICERF-V1") (pin "NRST") (pinfunction "NRST_NRST") (pintype "bidirectional"))
      (node (ref "MD1") (pin "11") (pinfunction "IO26_11") (pintype "bidirectional"))
    )
    (net (code "50") (name "RTS") (class "Default")
      (node (ref "Q1") (pin "2") (pinfunction "E_2") (pintype "passive"))
      (node (ref "R2") (pin "1") (pinfunction "1_1") (pintype "passive"))
      (node (ref "U$2") (pin "14") (pinfunction "RTS_14") (pintype "bidirectional"))
    )
    (net (code "51") (name "RX") (class "Default")
      (node (ref "D3") (pin "-") (pinfunction "-_-") (pintype "passive"))
      (node (ref "MD1") (pin "35") (pinfunction "TXD0_35") (pintype "bidirectional"))
      (node (ref "U$2") (pin "3") (pinfunction "RX_3") (pintype "bidirectional"))
    )
    (net (code "52") (name "RX_DB9") (class "Default")
      (node (ref "MD1") (pin "27") (pinfunction "IO16_27") (pintype "bidirectional"))
      (node (ref "U5") (pin "9") (pinfunction "R2OUT_9") (pintype "output"))
    )
    (net (code "53") (name "SCK_HSPI") (class "Default")
      (node (ref "MD1") (pin "13") (pinfunction "IO14_13") (pintype "bidirectional"))
      (node (ref "U$3") (pin "SCLK") (pinfunction "SCLK_SCLK") (pintype "bidirectional"))
    )
    (net (code "54") (name "SCK_VSPI") (class "Default")
      (node (ref "LORA-NICERF-V1") (pin "SCK") (pinfunction "SCK_SCK") (pintype "bidirectional"))
      (node (ref "MD1") (pin "30") (pinfunction "IO18_30") (pintype "bidirectional"))
    )
    (net (code "55") (name "SCL") (class "Default")
      (node (ref "R9") (pin "2") (pinfunction "2_2") (pintype "passive"))
      (node (ref "U2") (pin "6") (pinfunction "SCL_6") (pintype "input"))
      (node (ref "U3") (pin "6") (pinfunction "A_6") (pintype "bidirectional"))
    )
    (net (code "56") (name "SD0") (class "Default")
      (node (ref "MD1") (pin "21") (pinfunction "SD0_21") (pintype "bidirectional"))
    )
    (net (code "57") (name "SD1") (class "Default")
      (node (ref "MD1") (pin "22") (pinfunction "SD1_22") (pintype "bidirectional"))
    )
    (net (code "58") (name "SD2") (class "Default")
      (node (ref "MD1") (pin "17") (pinfunction "SD2_17") (pintype "bidirectional"))
    )
    (net (code "59") (name "SD3") (class "Default")
      (node (ref "MD1") (pin "18") (pinfunction "SD3_18") (pintype "bidirectional"))
    )
    (net (code "60") (name "SDA") (class "Default")
      (node (ref "R6") (pin "2") (pinfunction "2_2") (pintype "passive"))
      (node (ref "U2") (pin "5") (pinfunction "SDA_5") (pintype "bidirectional"))
      (node (ref "U3") (pin "5") (pinfunction "GND_5") (pintype "power_in"))
    )
    (net (code "61") (name "SENSOR_VN") (class "Default")
      (node (ref "MD1") (pin "5") (pinfunction "SENSOR_VN_5") (pintype "input"))
    )
    (net (code "62") (name "SENSOR_VP") (class "Default")
      (node (ref "MD1") (pin "4") (pinfunction "SENSOR_VP_4") (pintype "input"))
    )
    (net (code "63") (name "SS_LAN_CONV") (class "Default")
      (node (ref "MD1") (pin "26") (pinfunction "IO4_26") (pintype "bidirectional"))
      (node (ref "U$3") (pin "CS") (pinfunction "CS_CS") (pintype "bidirectional"))
    )
    (net (code "64") (name "SS_LORA") (class "Default")
      (node (ref "LORA-NICERF-V1") (pin "NSS") (pinfunction "NSS_NSS") (pintype "bidirectional"))
      (node (ref "MD1") (pin "29") (pinfunction "IO5_29") (pintype "bidirectional"))
    )
    (net (code "65") (name "T2OUT") (class "Default")
      (node (ref "J2") (pin "2") (pinfunction "2_2") (pintype "passive"))
      (node (ref "U5") (pin "7") (pinfunction "T2OUT_7") (pintype "output"))
    )
    (net (code "66") (name "TX") (class "Default")
      (node (ref "D2") (pin "-") (pinfunction "-_-") (pintype "passive"))
      (node (ref "MD1") (pin "34") (pinfunction "RXD0_34") (pintype "bidirectional"))
      (node (ref "U$2") (pin "2") (pinfunction "TX_2") (pintype "bidirectional"))
    )
    (net (code "67") (name "TX_DB9") (class "Default")
      (node (ref "MD1") (pin "28") (pinfunction "IO17_28") (pintype "bidirectional"))
      (node (ref "U5") (pin "10") (pinfunction "T2IN_10") (pintype "input"))
    )
    (net (code "68") (name "USB_N") (class "Default")
      (node (ref "J3") (pin "2") (pinfunction "D-_2") (pintype "bidirectional"))
      (node (ref "U$2") (pin "6") (pinfunction "D-_6") (pintype "bidirectional"))
    )
    (net (code "69") (name "USB_P") (class "Default")
      (node (ref "J3") (pin "3") (pinfunction "D+_3") (pintype "bidirectional"))
      (node (ref "U$2") (pin "5") (pinfunction "D+_5") (pintype "bidirectional"))
    )
    (net (code "70") (name "VCC") (class "Default")
      (node (ref "C1") (pin "1") (pinfunction "1_1") (pintype "passive"))
      (node (ref "C4") (pin "1") (pinfunction "1_1") (pintype "passive"))
      (node (ref "D5") (pin "A") (pinfunction "A_A") (pintype "passive"))
      (node (ref "J3") (pin "1") (pinfunction "VBUS_1") (pintype "power_in"))
      (node (ref "R4") (pin "2") (pinfunction "2_2") (pintype "passive"))
      (node (ref "R5") (pin "2") (pinfunction "2_2") (pintype "passive"))
      (node (ref "U$2") (pin "16") (pinfunction "VCC_16") (pintype "bidirectional"))
    )
    (net (code "71") (name "VCC_DB9") (class "Default")
      (node (ref "D6") (pin "C") (pinfunction "K_C") (pintype "passive"))
      (node (ref "J2") (pin "9") (pinfunction "9_9") (pintype "passive"))
      (node (ref "U$1") (pin "IN_VCC") (pinfunction "IN_VCC_IN_VCC") (pintype "bidirectional"))
    )
    (net (code "72") (name "unconnected-(J2-Pad1)") (class "Default")
      (node (ref "J2") (pin "1") (pinfunction "1_1") (pintype "passive"))
    )
    (net (code "73") (name "unconnected-(J2-Pad4)") (class "Default")
      (node (ref "J2") (pin "4") (pinfunction "4_4") (pintype "passive"))
    )
    (net (code "74") (name "unconnected-(J2-Pad6)") (class "Default")
      (node (ref "J2") (pin "6") (pinfunction "6_6") (pintype "passive"))
    )
    (net (code "75") (name "unconnected-(J2-Pad7)") (class "Default")
      (node (ref "J2") (pin "7") (pinfunction "7_7") (pintype "passive"))
    )
    (net (code "76") (name "unconnected-(J2-Pad8)") (class "Default")
      (node (ref "J2") (pin "8") (pinfunction "8_8") (pintype "passive"))
    )
    (net (code "77") (name "unconnected-(J3-ID-Pad4)") (class "Default")
      (node (ref "J3") (pin "4") (pinfunction "ID_4") (pintype "passive"))
    )
    (net (code "78") (name "unconnected-(JP3-Pad2)") (class "Default")
      (node (ref "JP3") (pin "2") (pinfunction "2_2") (pintype "passive"))
    )
    (net (code "79") (name "unconnected-(LORA-NICERF-V1-PadDIO2)") (class "Default")
      (node (ref "LORA-NICERF-V1") (pin "DIO2") (pinfunction "DIO2_DIO2") (pintype "bidirectional"))
    )
    (net (code "80") (name "unconnected-(LORA-NICERF-V1-PadNC)") (class "Default")
      (node (ref "LORA-NICERF-V1") (pin "NC") (pinfunction "NC_NC") (pintype "bidirectional"))
    )
    (net (code "81") (name "unconnected-(LORA-NICERF-V1-PadNC1)") (class "Default")
      (node (ref "LORA-NICERF-V1") (pin "NC1") (pinfunction "NC1_NC1") (pintype "bidirectional"))
    )
    (net (code "82") (name "unconnected-(MD1-IO2-Pad24)") (class "Default")
      (node (ref "MD1") (pin "24") (pinfunction "IO2_24") (pintype "bidirectional"))
    )
    (net (code "83") (name "unconnected-(MD1-IO33-Pad9)") (class "Default")
      (node (ref "MD1") (pin "9") (pinfunction "IO33_9") (pintype "bidirectional"))
    )
    (net (code "84") (name "unconnected-(U$2-CTS-Pad9)") (class "Default")
      (node (ref "U$2") (pin "9") (pinfunction "CTS_9") (pintype "bidirectional"))
    )
    (net (code "85") (name "unconnected-(U$2-DCD-Pad12)") (class "Default")
      (node (ref "U$2") (pin "12") (pinfunction "DCD_12") (pintype "bidirectional"))
    )
    (net (code "86") (name "unconnected-(U$2-DSR-Pad10)") (class "Default")
      (node (ref "U$2") (pin "10") (pinfunction "DSR_10") (pintype "bidirectional"))
    )
    (net (code "87") (name "unconnected-(U$2-RI-Pad11)") (class "Default")
      (node (ref "U$2") (pin "11") (pinfunction "RI_11") (pintype "bidirectional"))
    )
    (net (code "88") (name "unconnected-(U$2-RS232-Pad15)") (class "Default")
      (node (ref "U$2") (pin "15") (pinfunction "RS232_15") (pintype "bidirectional"))
    )
    (net (code "89") (name "unconnected-(U$3-PadNC)") (class "Default")
      (node (ref "U$3") (pin "NC") (pinfunction "NC_NC") (pintype "bidirectional"))
    )
    (net (code "90") (name "unconnected-(U5-R1IN-Pad13)") (class "Default")
      (node (ref "U5") (pin "13") (pinfunction "R1IN_13") (pintype "input"))
    )
    (net (code "91") (name "unconnected-(U5-R1OUT-Pad12)") (class "Default")
      (node (ref "U5") (pin "12") (pinfunction "R1OUT_12") (pintype "output"))
    )
    (net (code "92") (name "unconnected-(U5-T1IN-Pad11)") (class "Default")
      (node (ref "U5") (pin "11") (pinfunction "T1IN_11") (pintype "input"))
    )
    (net (code "93") (name "unconnected-(U5-T1OUT-Pad14)") (class "Default")
      (node (ref "U5") (pin "14") (pinfunction "T1OUT_14") (pintype "output"))
    )
  )
)
